# IR_POWER_STAGE.net
KiCad netlist of a schematic drawn in Altium Designer
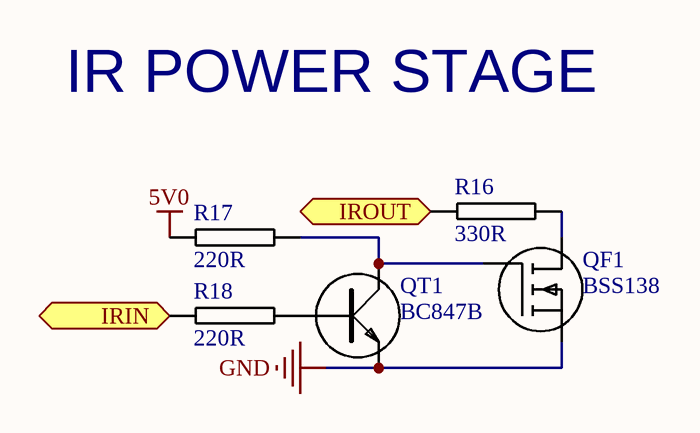
[diagram p0: IR POWER STAGE.SchDoc]

(export (version "E")
  (design (tool "Eeschema 10.0.6"))
  (components
    (comp (ref "QF1")
      (value "BSS138")
      (footprint "SOT23-GDS")
      (description "N CHANNEL MOSFET BSS138 SOT23")
      (fields
        (field (name "MANUFACTURER") "Fairchild Semiconductor")
        (field (name "MANUFACTURER PART NUMBER") "2N7002")
      )
      (libsource (lib "RVA_Silicon Switch_Silicon_MOSFET_N-Channel") (part "BSS138-SOT23"))
    )
    (comp (ref "QT1")
      (value "BC847B")
      (footprint "SOT23-BCE")
      (description "BC847 SMALL SIGNAL NPN TRANSISTOR")
      (fields
        (field (name "MANUFACTURER PART NUMBER") "BC847BMTF")
        (field (name "MANUFACTURER") "Fairchild Semiconductor")
      )
      (libsource (lib "vh_altium_library") (part "BC847"))
    )
    (comp (ref "R16")
      (value "330R")
      (footprint "0805R-330")
      (description "RESISTOR 0805 1/4 WATT THIN FILM")
      (libsource (lib "RVA_Altium_Library") (part "0805R-330"))
    )
    (comp (ref "R17")
      (value "220R")
      (footprint "0805R-220")
      (description "RESISTOR 0805 1/4 WATT THIN FILM")
      (libsource (lib "RVA_Altium_Library") (part "0805R-220"))
    )
    (comp (ref "R18")
      (value "220R")
      (footprint "0805R-220")
      (description "RESISTOR 0805 1/4 WATT THIN FILM")
      (libsource (lib "RVA_Altium_Library") (part "0805R-220"))
    )
  )
  (nets
    (net (code "1") (name "/IRIN") (class "Default") (node (ref "R18") (pin "1") (pintype "passive")))
    (net (code "2") (name "/IROUT") (class "Default") (node (ref "R16") (pin "1") (pintype "passive")))
    (net (code "3") (name "5V0") (class "Default") (node (ref "R17") (pin "1") (pintype "passive")))
    (net (code "4") (name "GND") (class "Default")
      (node (ref "QF1") (pin "S") (pintype "passive"))
      (node (ref "QT1") (pin "E") (pintype "passive"))
    )
    (net (code "5") (name "Net-(QF1-PadD)") (class "Default")
      (node (ref "QF1") (pin "D") (pintype "passive"))
      (node (ref "R16") (pin "2") (pintype "passive"))
    )
    (net (code "6") (name "Net-(QF1-PadG)") (class "Default")
      (node (ref "QF1") (pin "G") (pintype "passive"))
      (node (ref "QT1") (pin "C") (pintype "passive"))
      (node (ref "R17") (pin "2") (pintype "passive"))
    )
    (net (code "7") (name "Net-(QT1-PadB)") (class "Default")
      (node (ref "QT1") (pin "B") (pintype "passive"))
      (node (ref "R18") (pin "2") (pintype "passive"))
    )
  )
)
